# INPUT_PROTECTION.net
KiCad netlist of a schematic drawn in Altium Designer
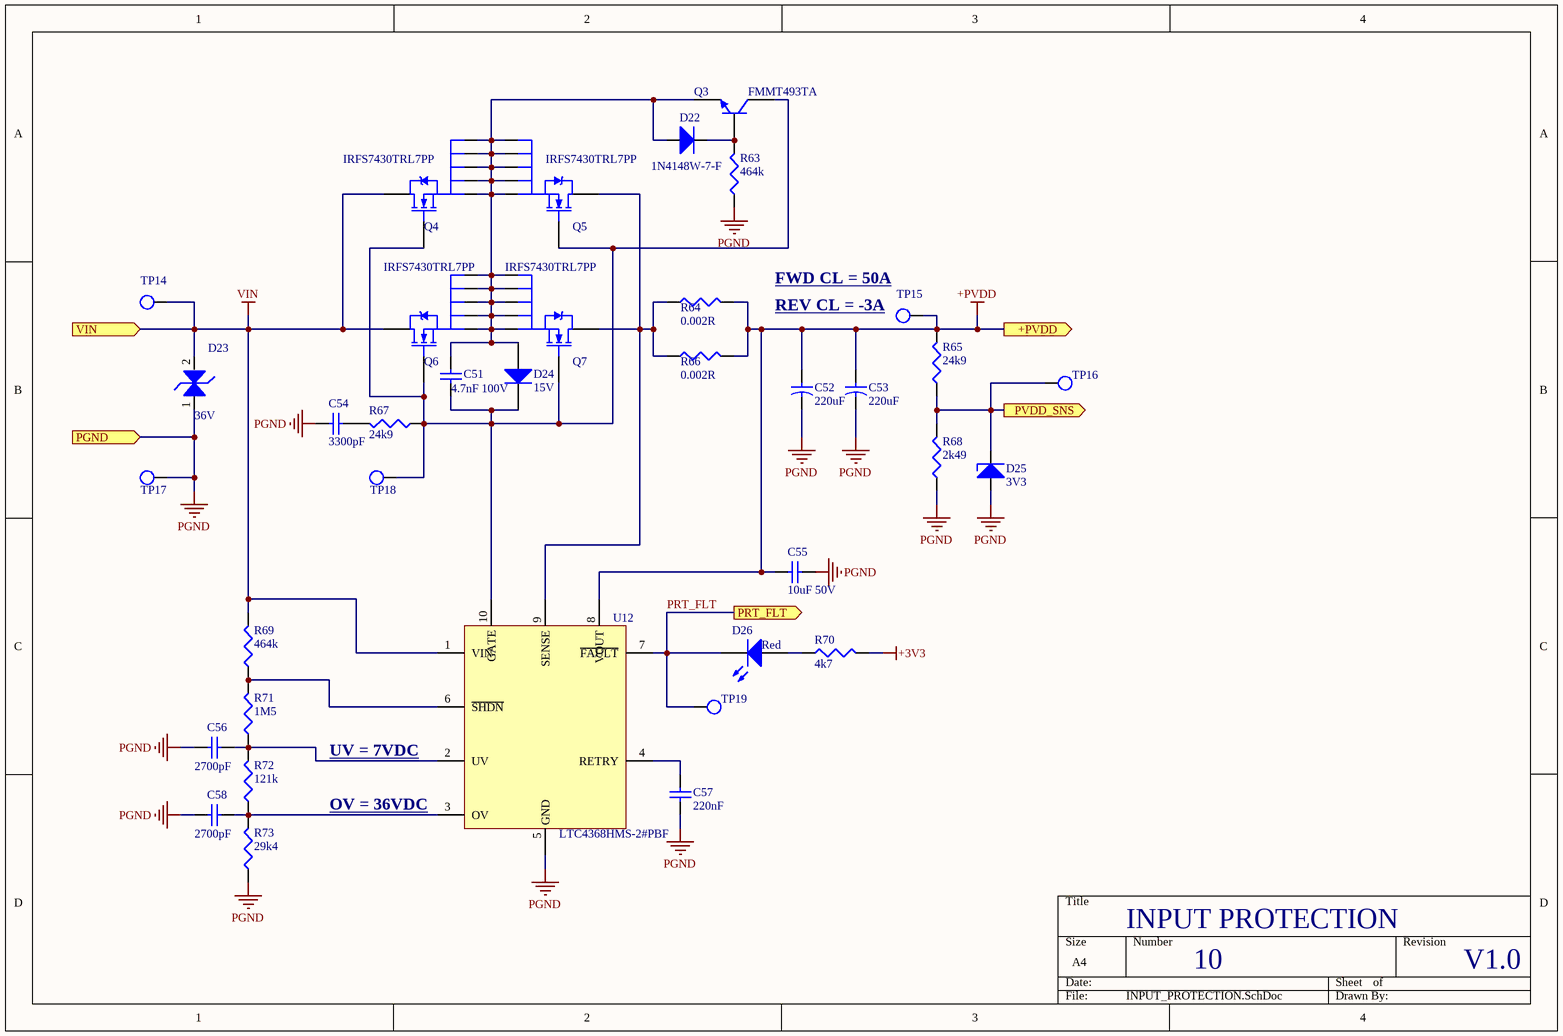
[diagram p0: INPUT_PROTECTION.SchDoc]

(export (version "E")
  (design (tool "Eeschema 10.0.6"))
  (components
    (comp (ref "C51")
      (value "4.7nF 100V")
      (footprint "CAP1206")
      (description "CAP CER 4700PF 100V X7R 1206")
      (libsource (lib "CAP_Library") (part "CAP1206_4.7nF_100V"))
    )
    (comp (ref "C52")
      (value "220uF")
      (footprint "CAP_RADIAL_SMD_10x10")
      (description "CAP ALUM 220UF 20% 50V SMD")
      (libsource (lib "CAP_Library") (part "CAP_RADIAL_EEE-FK1H221GP"))
    )
    (comp (ref "C53")
      (value "220uF")
      (footprint "CAP_RADIAL_SMD_10x10")
      (description "CAP ALUM 220UF 20% 50V SMD")
      (libsource (lib "CAP_Library") (part "CAP_RADIAL_EEE-FK1H221GP"))
    )
    (comp (ref "C54")
      (value "3300pF")
      (footprint "CAP0805")
      (description "CAP CER 3300PF 100V X7R 0805")
      (libsource (lib "CAP_Library") (part "CAP0805_3300pF"))
    )
    (comp (ref "C55")
      (value "10uF 50V")
      (footprint "CAP1206")
      (description "CAP CER 10UF 50V X7R 1206")
      (libsource (lib "CAP_Library") (part "CAP1206_10uF"))
    )
    (comp (ref "C56")
      (value "2700pF")
      (footprint "CAP0603")
      (description "CAP CER 1200PF 50V X7R 0603")
      (libsource (lib "CAP_Library") (part "CAP0603_2700pF"))
    )
    (comp (ref "C57")
      (value "220nF")
      (footprint "CAP0603")
      (description "CAP CER 0.22UF 50V X7R 0603")
      (libsource (lib "CAP_Library") (part "CAP0603_220n"))
    )
    (comp (ref "C58")
      (value "2700pF")
      (footprint "CAP0603")
      (description "CAP CER 1200PF 50V X7R 0603")
      (libsource (lib "CAP_Library") (part "CAP0603_2700pF"))
    )
    (comp (ref "D22")
      (value "100V 300mA")
      (footprint "SOD123_1N4148W-7-F")
      (description "DIODE GEN PURP 100V 300MA SOD123")
      (fields (field (name "P/N") "1N4148W-7-F"))
      (libsource (lib "DIODE_Library") (part "DIODE_1N4148W-7-F"))
    )
    (comp (ref "D23")
      (value "36V")
      (footprint "DO214AA")
      (description "TVS DIODE 36V DO214AA")
      (libsource (lib "DIODE_Library") (part "SMBJ36CA-TR_TVS_BI_DIR"))
    )
    (comp (ref "D24")
      (value "15V")
      (footprint "SOD128_PMEG10030ELPX")
      (description "DIODE ZENER 15V 2W TMINIP2")
      (libsource (lib "DIODE_Library") (part "ZNR_DZ2415000L"))
    )
    (comp (ref "D25")
      (value "3V3")
      (footprint "SOD323")
      (description "DIODE ZENER 3.3V 300MW SOD323")
      (libsource (lib "DIODE_Library") (part "ZENER_3V3_MM3Z3V3T1G"))
    )
    (comp (ref "D26")
      (value "Red")
      (footprint "LED0603")
      (description "LED RED CLEAR 0603 SMD")
      (libsource (lib "MISC_Library") (part "LED0603_RED"))
    )
    (comp (ref "Q3")
      (value "100V 1A")
      (footprint "SOT23_FMMT493TA")
      (description "TRANS NPN 100V 1A SOT23-3")
      (fields (field (name "P/N") "FMMT493TA"))
      (libsource (lib "Mosfet_Library") (part "FMMT493TA_NPN"))
    )
    (comp (ref "Q4")
      (value "NMOS")
      (footprint "TO263-7_INFINEON")
      (description "MOSFET N-CH 40V 240A D2PAK")
      (fields (field (name "P/N") "IRFS7430TRL7PP"))
      (libsource (lib "Mosfet_Library") (part "IRFS7430TRL7PP_NMOS"))
    )
    (comp (ref "Q5")
      (value "NMOS")
      (footprint "TO263-7_INFINEON")
      (description "MOSFET N-CH 40V 240A D2PAK")
      (fields (field (name "P/N") "IRFS7430TRL7PP"))
      (libsource (lib "Mosfet_Library") (part "IRFS7430TRL7PP_NMOS"))
    )
    (comp (ref "Q6")
      (value "NMOS")
      (footprint "TO263-7_INFINEON")
      (description "MOSFET N-CH 40V 240A D2PAK")
      (fields (field (name "P/N") "IRFS7430TRL7PP"))
      (libsource (lib "Mosfet_Library") (part "IRFS7430TRL7PP_NMOS"))
    )
    (comp (ref "Q7")
      (value "NMOS")
      (footprint "TO263-7_INFINEON")
      (description "MOSFET N-CH 40V 240A D2PAK")
      (fields (field (name "P/N") "IRFS7430TRL7PP"))
      (libsource (lib "Mosfet_Library") (part "IRFS7430TRL7PP_NMOS"))
    )
    (comp (ref "R63")
      (value "464k")
      (footprint "RES0603")
      (description "RES 464K OHM 1% 1/10W 0603")
      (libsource (lib "RES_Library") (part "RES0603_464k"))
    )
    (comp (ref "R64")
      (value "0.002R")
      (footprint "RES2512_WSLF_SERIES")
      (description "RES 0.002 OHM 1% 5W 2512")
      (libsource (lib "RES_Library") (part "RES2512_2mR"))
    )
    (comp (ref "R65")
      (value "24k9")
      (footprint "RES0603")
      (description "RES SMD 24.9K OHM 1% 1/10W 0603")
      (libsource (lib "RES_Library") (part "RES0603_24k9"))
    )
    (comp (ref "R66")
      (value "0.002R")
      (footprint "RES2512_WSLF_SERIES")
      (description "RES 0.002 OHM 1% 5W 2512")
      (libsource (lib "RES_Library") (part "RES2512_2mR"))
    )
    (comp (ref "R67")
      (value "24k9")
      (footprint "RES0603")
      (description "RES SMD 24.9K OHM 1% 1/10W 0603")
      (libsource (lib "RES_Library") (part "RES0603_24k9"))
    )
    (comp (ref "R68")
      (value "2k49")
      (footprint "RES0603")
      (description "RES 2.49K OHM 1% 1/10W 0603")
      (libsource (lib "RES_Library") (part "RES0603_2k49"))
    )
    (comp (ref "R69")
      (value "464k")
      (footprint "RES0603")
      (description "RES 464K OHM 1% 1/10W 0603")
      (libsource (lib "RES_Library") (part "RES0603_464k"))
    )
    (comp (ref "R70")
      (value "4k7")
      (footprint "RES0603")
      (description "RES SMD 4.7K OHM 1% 1/10W 0603")
      (libsource (lib "RES_Library") (part "RES0603_4k7"))
    )
    (comp (ref "R71")
      (value "1M5")
      (footprint "RES0603")
      (description "RES 1.5M OHM 1% 1/10W 0603")
      (libsource (lib "RES_Library") (part "RES0603_1M5"))
    )
    (comp (ref "R72")
      (value "121k")
      (footprint "RES0603")
      (description "RES 121K OHM 1% 1/10W 0603")
      (libsource (lib "RES_Library") (part "RES0603_121k"))
    )
    (comp (ref "R73")
      (value "29k4")
      (footprint "RES0603")
      (description "RES SMD 29.4K OHM 1% 1/10W 0603")
      (libsource (lib "RES_Library") (part "RES0603_29k4"))
    )
    (comp (ref "TP14")
      (value "TEST_POINT")
      (footprint "TEST_POINT_TH")
      (libsource (lib "MISC_Library") (part "TEST_POINT"))
    )
    (comp (ref "TP15")
      (value "TEST_POINT")
      (footprint "TEST_POINT_TH")
      (libsource (lib "MISC_Library") (part "TEST_POINT"))
    )
    (comp (ref "TP16")
      (value "TEST_POINT")
      (footprint "TEST_POINT_TH")
      (libsource (lib "MISC_Library") (part "TEST_POINT"))
    )
    (comp (ref "TP17")
      (value "TEST_POINT")
      (footprint "TEST_POINT_TH")
      (libsource (lib "MISC_Library") (part "TEST_POINT"))
    )
    (comp (ref "TP18")
      (value "TEST_POINT")
      (footprint "TEST_POINT_TH")
      (libsource (lib "MISC_Library") (part "TEST_POINT"))
    )
    (comp (ref "TP19")
      (value "TEST_POINT")
      (footprint "TEST_POINT_TH")
      (libsource (lib "MISC_Library") (part "TEST_POINT"))
    )
    (comp (ref "U12")
      (value "ADJ")
      (footprint "MSOP10")
      (description "IC SURGE SUPPRESSION ADJ 10MSOP")
      (fields (field (name "P/N") "LTC4368HMS-2#PBF"))
      (libsource (lib "IC_Library") (part "LTC4368HMS-2#PBF"))
    )
  )
  (nets
    (net (code "1") (name "+3V3") (class "Default")
      (node (ref "R70") (pin "2") (pinfunction "2_2") (pintype "passive"))
    )
    (net (code "2") (name "+PVDD") (class "Default")
      (node (ref "C52") (pin "1") (pinfunction "1_1") (pintype "passive"))
      (node (ref "C53") (pin "1") (pinfunction "1_1") (pintype "passive"))
      (node (ref "C55") (pin "2") (pinfunction "2_2") (pintype "passive"))
      (node (ref "R64") (pin "2") (pinfunction "2_2") (pintype "passive"))
      (node (ref "R65") (pin "2") (pinfunction "2_2") (pintype "passive"))
      (node (ref "R66") (pin "2") (pinfunction "2_2") (pintype "passive"))
      (node (ref "TP15") (pin "1") (pinfunction "1_1") (pintype "passive"))
      (node (ref "U12") (pin "8") (pinfunction "VOUT_8") (pintype "passive"))
    )
    (net (code "3") (name "/PRT_FLT") (class "Default")
      (node (ref "D26") (pin "2") (pinfunction "K_2") (pintype "passive"))
      (node (ref "TP19") (pin "1") (pinfunction "1_1") (pintype "passive"))
      (node (ref "U12") (pin "7") (pinfunction "~{FAULT}_7") (pintype "passive"))
    )
    (net (code "4") (name "/PVDD_SNS") (class "Default")
      (node (ref "D25") (pin "1") (pinfunction "K_1") (pintype "passive"))
      (node (ref "R65") (pin "1") (pinfunction "1_1") (pintype "passive"))
      (node (ref "R68") (pin "2") (pinfunction "2_2") (pintype "passive"))
      (node (ref "TP16") (pin "1") (pinfunction "1_1") (pintype "passive"))
    )
    (net (code "5") (name "Net-(C54-Pad2)") (class "Default")
      (node (ref "C54") (pin "2") (pinfunction "2_2") (pintype "passive"))
      (node (ref "R67") (pin "2") (pinfunction "2_2") (pintype "passive"))
    )
    (net (code "6") (name "Net-(D22-A)") (class "Default")
      (node (ref "C51") (pin "2") (pinfunction "2_2") (pintype "passive"))
      (node (ref "D22") (pin "1") (pinfunction "A_1") (pintype "passive"))
      (node (ref "D24") (pin "1") (pinfunction "A_1") (pintype "passive"))
      (node (ref "Q3") (pin "1") (pinfunction "E_1") (pintype "passive"))
      (node (ref "Q4") (pin "2") (pinfunction "S_2") (pintype "passive"))
      (node (ref "Q4") (pin "3") (pinfunction "S_3") (pintype "passive"))
      (node (ref "Q4") (pin "5") (pinfunction "S_5") (pintype "passive"))
      (node (ref "Q4") (pin "6") (pinfunction "S_6") (pintype "passive"))
      (node (ref "Q4") (pin "7") (pinfunction "S_7") (pintype "passive"))
      (node (ref "Q5") (pin "2") (pinfunction "S_2") (pintype "passive"))
      (node (ref "Q5") (pin "3") (pinfunction "S_3") (pintype "passive"))
      (node (ref "Q5") (pin "5") (pinfunction "S_5") (pintype "passive"))
      (node (ref "Q5") (pin "6") (pinfunction "S_6") (pintype "passive"))
      (node (ref "Q5") (pin "7") (pinfunction "S_7") (pintype "passive"))
      (node (ref "Q6") (pin "2") (pinfunction "S_2") (pintype "passive"))
      (node (ref "Q6") (pin "3") (pinfunction "S_3") (pintype "passive"))
      (node (ref "Q6") (pin "5") (pinfunction "S_5") (pintype "passive"))
      (node (ref "Q6") (pin "6") (pinfunction "S_6") (pintype "passive"))
      (node (ref "Q6") (pin "7") (pinfunction "S_7") (pintype "passive"))
      (node (ref "Q7") (pin "2") (pinfunction "S_2") (pintype "passive"))
      (node (ref "Q7") (pin "3") (pinfunction "S_3") (pintype "passive"))
      (node (ref "Q7") (pin "5") (pinfunction "S_5") (pintype "passive"))
      (node (ref "Q7") (pin "6") (pinfunction "S_6") (pintype "passive"))
      (node (ref "Q7") (pin "7") (pinfunction "S_7") (pintype "passive"))
    )
    (net (code "7") (name "Net-(D22-K)") (class "Default")
      (node (ref "D22") (pin "2") (pinfunction "K_2") (pintype "passive"))
      (node (ref "Q3") (pin "2") (pinfunction "B_2") (pintype "passive"))
      (node (ref "R63") (pin "2") (pinfunction "2_2") (pintype "passive"))
    )
    (net (code "8") (name "Net-(D24-K)") (class "Default")
      (node (ref "C51") (pin "1") (pinfunction "1_1") (pintype "passive"))
      (node (ref "D24") (pin "2") (pinfunction "K_2") (pintype "passive"))
      (node (ref "Q3") (pin "3") (pinfunction "C_3") (pintype "passive"))
      (node (ref "Q4") (pin "1") (pinfunction "G_1") (pintype "passive"))
      (node (ref "Q5") (pin "1") (pinfunction "G_1") (pintype "passive"))
      (node (ref "Q6") (pin "1") (pinfunction "G_1") (pintype "passive"))
      (node (ref "Q7") (pin "1") (pinfunction "G_1") (pintype "passive"))
      (node (ref "R67") (pin "1") (pinfunction "1_1") (pintype "passive"))
      (node (ref "TP18") (pin "1") (pinfunction "1_1") (pintype "passive"))
      (node (ref "U12") (pin "10") (pinfunction "GATE_10") (pintype "passive"))
    )
    (net (code "9") (name "Net-(D26-A)") (class "Default")
      (node (ref "D26") (pin "1") (pinfunction "A_1") (pintype "passive"))
      (node (ref "R70") (pin "1") (pinfunction "1_1") (pintype "passive"))
    )
    (net (code "10") (name "Net-(Q5-D)") (class "Default")
      (node (ref "Q5") (pin "8") (pinfunction "D_8") (pintype "passive"))
      (node (ref "Q7") (pin "8") (pinfunction "D_8") (pintype "passive"))
      (node (ref "R64") (pin "1") (pinfunction "1_1") (pintype "passive"))
      (node (ref "R66") (pin "1") (pinfunction "1_1") (pintype "passive"))
      (node (ref "U12") (pin "9") (pinfunction "SENSE_9") (pintype "passive"))
    )
    (net (code "11") (name "Net-(U12-OV)") (class "Default")
      (node (ref "C58") (pin "2") (pinfunction "2_2") (pintype "passive"))
      (node (ref "R72") (pin "1") (pinfunction "1_1") (pintype "passive"))
      (node (ref "R73") (pin "2") (pinfunction "2_2") (pintype "passive"))
      (node (ref "U12") (pin "3") (pinfunction "OV_3") (pintype "passive"))
    )
    (net (code "12") (name "Net-(U12-RETRY)") (class "Default")
      (node (ref "C57") (pin "2") (pinfunction "2_2") (pintype "passive"))
      (node (ref "U12") (pin "4") (pinfunction "RETRY_4") (pintype "passive"))
    )
    (net (code "13") (name "Net-(U12-UV)") (class "Default")
      (node (ref "C56") (pin "2") (pinfunction "2_2") (pintype "passive"))
      (node (ref "R71") (pin "1") (pinfunction "1_1") (pintype "passive"))
      (node (ref "R72") (pin "2") (pinfunction "2_2") (pintype "passive"))
      (node (ref "U12") (pin "2") (pinfunction "UV_2") (pintype "passive"))
    )
    (net (code "14") (name "Net-(U12-~{SHDN})") (class "Default")
      (node (ref "R69") (pin "1") (pinfunction "1_1") (pintype "passive"))
      (node (ref "R71") (pin "2") (pinfunction "2_2") (pintype "passive"))
      (node (ref "U12") (pin "6") (pinfunction "~{SHDN}_6") (pintype "passive"))
    )
    (net (code "15") (name "PGND") (class "Default")
      (node (ref "C52") (pin "2") (pinfunction "2_2") (pintype "passive"))
      (node (ref "C53") (pin "2") (pinfunction "2_2") (pintype "passive"))
      (node (ref "C54") (pin "1") (pinfunction "1_1") (pintype "passive"))
      (node (ref "C55") (pin "1") (pinfunction "1_1") (pintype "passive"))
      (node (ref "C56") (pin "1") (pinfunction "1_1") (pintype "passive"))
      (node (ref "C57") (pin "1") (pinfunction "1_1") (pintype "passive"))
      (node (ref "C58") (pin "1") (pinfunction "1_1") (pintype "passive"))
      (node (ref "D23") (pin "1") (pinfunction "1_1") (pintype "passive"))
      (node (ref "D25") (pin "2") (pinfunction "A_2") (pintype "passive"))
      (node (ref "R63") (pin "1") (pinfunction "1_1") (pintype "passive"))
      (node (ref "R68") (pin "1") (pinfunction "1_1") (pintype "passive"))
      (node (ref "R73") (pin "1") (pinfunction "1_1") (pintype "passive"))
      (node (ref "TP17") (pin "1") (pinfunction "1_1") (pintype "passive"))
      (node (ref "U12") (pin "5") (pinfunction "GND_5") (pintype "passive"))
    )
    (net (code "16") (name "VIN") (class "Default")
      (node (ref "D23") (pin "2") (pinfunction "2_2") (pintype "passive"))
      (node (ref "Q4") (pin "8") (pinfunction "D_8") (pintype "passive"))
      (node (ref "Q6") (pin "8") (pinfunction "D_8") (pintype "passive"))
      (node (ref "R69") (pin "2") (pinfunction "2_2") (pintype "passive"))
      (node (ref "TP14") (pin "1") (pinfunction "1_1") (pintype "passive"))
      (node (ref "U12") (pin "1") (pinfunction "VIN_1") (pintype "passive"))
    )
  )
)
